# SDRAM.net
KiCad netlist of a schematic drawn in Altium Designer
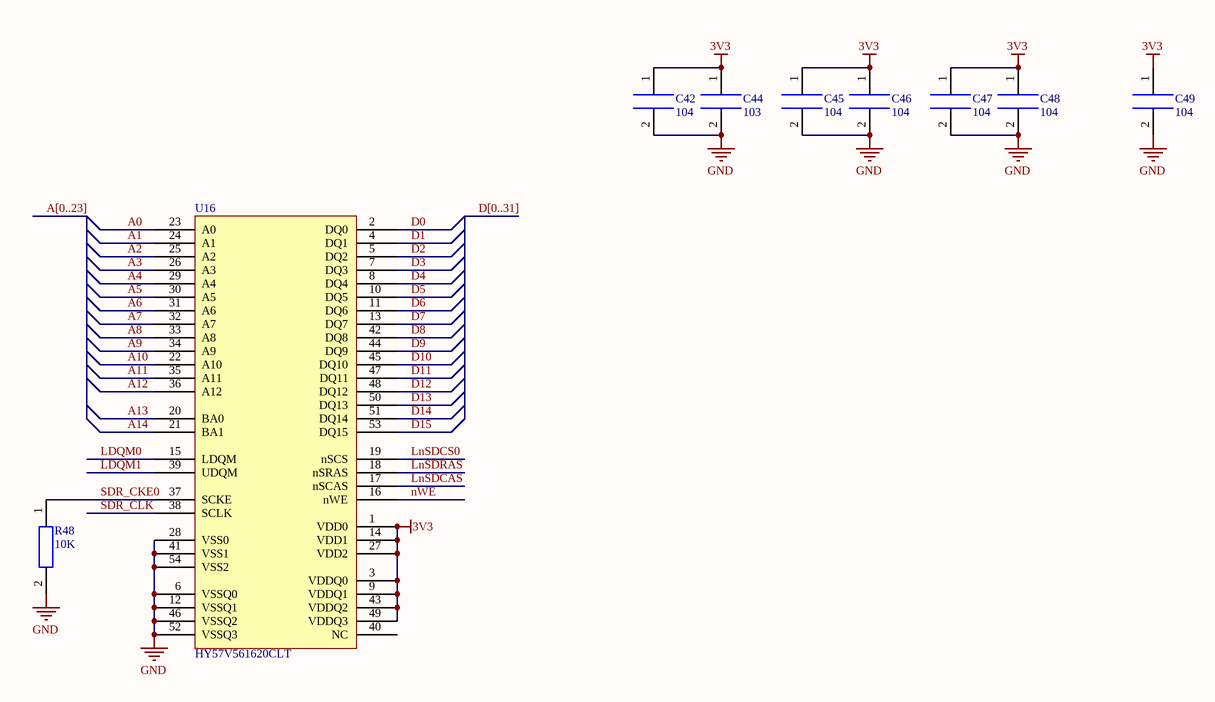
[diagram p0: SDRAM.SchDoc]

(export (version "E")
  (design (tool "Eeschema 10.0.6"))
  (components
    (comp (ref "C42") (value "104") (footprint "0603C") (libsource (lib "MyProject1") (part "CAP")))
    (comp (ref "C44") (value "103") (footprint "0603C") (libsource (lib "MyProject1") (part "CAP")))
    (comp (ref "C45") (value "104") (footprint "0603C") (libsource (lib "MyProject1") (part "CAP")))
    (comp (ref "C46") (value "104") (footprint "0603C") (libsource (lib "MyProject1") (part "CAP")))
    (comp (ref "C47") (value "104") (footprint "0603C") (libsource (lib "MyProject1") (part "CAP")))
    (comp (ref "C48") (value "104") (footprint "0603C") (libsource (lib "MyProject1") (part "CAP")))
    (comp (ref "C49") (value "104") (footprint "0603C") (libsource (lib "MyProject1") (part "CAP")))
    (comp (ref "R48") (value "10K") (footprint "0603R") (libsource (lib "MyProject1") (part "RES")))
    (comp (ref "U16")
      (value "HY57V561620CLT")
      (footprint "TSSOP-54")
      (libsource (lib "MyProject1") (part "HY57V561620CLT"))
    )
  )
  (nets
    (net (code "26") (name "/A0") (class "Default")
      (node (ref "U16") (pin "23") (pinfunction "A0_23") (pintype "passive"))
    )
    (net (code "27") (name "/A1") (class "Default")
      (node (ref "U16") (pin "24") (pinfunction "A1_24") (pintype "passive"))
    )
    (net (code "28") (name "/A2") (class "Default")
      (node (ref "U16") (pin "25") (pinfunction "A2_25") (pintype "passive"))
    )
    (net (code "29") (name "/A3") (class "Default")
      (node (ref "U16") (pin "26") (pinfunction "A3_26") (pintype "passive"))
    )
    (net (code "30") (name "/A4") (class "Default")
      (node (ref "U16") (pin "29") (pinfunction "A4_29") (pintype "passive"))
    )
    (net (code "31") (name "/A5") (class "Default")
      (node (ref "U16") (pin "30") (pinfunction "A5_30") (pintype "passive"))
    )
    (net (code "32") (name "/A6") (class "Default")
      (node (ref "U16") (pin "31") (pinfunction "A6_31") (pintype "passive"))
    )
    (net (code "33") (name "/A7") (class "Default")
      (node (ref "U16") (pin "32") (pinfunction "A7_32") (pintype "passive"))
    )
    (net (code "34") (name "/A8") (class "Default")
      (node (ref "U16") (pin "33") (pinfunction "A8_33") (pintype "passive"))
    )
    (net (code "35") (name "/A9") (class "Default")
      (node (ref "U16") (pin "34") (pinfunction "A9_34") (pintype "passive"))
    )
    (net (code "36") (name "/A10") (class "Default")
      (node (ref "U16") (pin "22") (pinfunction "A10_22") (pintype "passive"))
    )
    (net (code "37") (name "/A11") (class "Default")
      (node (ref "U16") (pin "35") (pinfunction "A11_35") (pintype "passive"))
    )
    (net (code "38") (name "/A12") (class "Default")
      (node (ref "U16") (pin "36") (pinfunction "A12_36") (pintype "passive"))
    )
    (net (code "39") (name "/A13") (class "Default")
      (node (ref "U16") (pin "20") (pinfunction "BA0_20") (pintype "passive"))
    )
    (net (code "40") (name "/A14") (class "Default")
      (node (ref "U16") (pin "21") (pinfunction "BA1_21") (pintype "passive"))
    )
    (net (code "42") (name "/D0") (class "Default")
      (node (ref "U16") (pin "2") (pinfunction "DQ0_2") (pintype "passive"))
    )
    (net (code "43") (name "/D1") (class "Default")
      (node (ref "U16") (pin "4") (pinfunction "DQ1_4") (pintype "passive"))
    )
    (net (code "44") (name "/D2") (class "Default")
      (node (ref "U16") (pin "5") (pinfunction "DQ2_5") (pintype "passive"))
    )
    (net (code "45") (name "/D3") (class "Default")
      (node (ref "U16") (pin "7") (pinfunction "DQ3_7") (pintype "passive"))
    )
    (net (code "46") (name "/D4") (class "Default")
      (node (ref "U16") (pin "8") (pinfunction "DQ4_8") (pintype "passive"))
    )
    (net (code "47") (name "/D5") (class "Default")
      (node (ref "U16") (pin "10") (pinfunction "DQ5_10") (pintype "passive"))
    )
    (net (code "48") (name "/D6") (class "Default")
      (node (ref "U16") (pin "11") (pinfunction "DQ6_11") (pintype "passive"))
    )
    (net (code "49") (name "/D7") (class "Default")
      (node (ref "U16") (pin "13") (pinfunction "DQ7_13") (pintype "passive"))
    )
    (net (code "50") (name "/D8") (class "Default")
      (node (ref "U16") (pin "42") (pinfunction "DQ8_42") (pintype "passive"))
    )
    (net (code "51") (name "/D9") (class "Default")
      (node (ref "U16") (pin "44") (pinfunction "DQ9_44") (pintype "passive"))
    )
    (net (code "52") (name "/D10") (class "Default")
      (node (ref "U16") (pin "45") (pinfunction "DQ10_45") (pintype "passive"))
    )
    (net (code "53") (name "/D11") (class "Default")
      (node (ref "U16") (pin "47") (pinfunction "DQ11_47") (pintype "passive"))
    )
    (net (code "54") (name "/D12") (class "Default")
      (node (ref "U16") (pin "48") (pinfunction "DQ12_48") (pintype "passive"))
    )
    (net (code "55") (name "/D13") (class "Default")
      (node (ref "U16") (pin "50") (pinfunction "DQ13_50") (pintype "passive"))
    )
    (net (code "56") (name "/D14") (class "Default")
      (node (ref "U16") (pin "51") (pinfunction "DQ14_51") (pintype "passive"))
    )
    (net (code "57") (name "/D15") (class "Default")
      (node (ref "U16") (pin "53") (pinfunction "DQ15_53") (pintype "passive"))
    )
    (net (code "59") (name "/LDQM0") (class "Default")
      (node (ref "U16") (pin "15") (pinfunction "LDQM_15") (pintype "passive"))
    )
    (net (code "60") (name "/LDQM1") (class "Default")
      (node (ref "U16") (pin "39") (pinfunction "UDQM_39") (pintype "passive"))
    )
    (net (code "61") (name "/LnSDCAS") (class "Default")
      (node (ref "U16") (pin "17") (pinfunction "nSCAS_17") (pintype "passive"))
    )
    (net (code "62") (name "/LnSDCS0") (class "Default")
      (node (ref "U16") (pin "19") (pinfunction "nSCS_19") (pintype "passive"))
    )
    (net (code "63") (name "/LnSDRAS") (class "Default")
      (node (ref "U16") (pin "18") (pinfunction "nSRAS_18") (pintype "passive"))
    )
    (net (code "64") (name "/SDR_CKE0") (class "Default")
      (node (ref "R48") (pin "1") (pinfunction "1_1") (pintype "passive"))
      (node (ref "U16") (pin "37") (pinfunction "SCKE_37") (pintype "passive"))
    )
    (net (code "65") (name "/SDR_CLK") (class "Default")
      (node (ref "U16") (pin "38") (pinfunction "SCLK_38") (pintype "passive"))
    )
    (net (code "66") (name "/nWE") (class "Default")
      (node (ref "U16") (pin "16") (pinfunction "nWE_16") (pintype "passive"))
    )
    (net (code "67") (name "3V3") (class "Default")
      (node (ref "C42") (pin "1") (pinfunction "1_1") (pintype "passive"))
      (node (ref "C44") (pin "1") (pinfunction "1_1") (pintype "passive"))
      (node (ref "C45") (pin "1") (pinfunction "1_1") (pintype "passive"))
      (node (ref "C46") (pin "1") (pinfunction "1_1") (pintype "passive"))
      (node (ref "C47") (pin "1") (pinfunction "1_1") (pintype "passive"))
      (node (ref "C48") (pin "1") (pinfunction "1_1") (pintype "passive"))
      (node (ref "C49") (pin "1") (pinfunction "1_1") (pintype "passive"))
      (node (ref "U16") (pin "1") (pinfunction "VDD0_1") (pintype "passive"))
      (node (ref "U16") (pin "14") (pinfunction "VDD1_14") (pintype "passive"))
      (node (ref "U16") (pin "27") (pinfunction "VDD2_27") (pintype "passive"))
      (node (ref "U16") (pin "3") (pinfunction "VDDQ0_3") (pintype "passive"))
      (node (ref "U16") (pin "43") (pinfunction "VDDQ2_43") (pintype "passive"))
      (node (ref "U16") (pin "49") (pinfunction "VDDQ3_49") (pintype "passive"))
      (node (ref "U16") (pin "9") (pinfunction "VDDQ1_9") (pintype "passive"))
    )
    (net (code "68") (name "GND") (class "Default")
      (node (ref "C42") (pin "2") (pinfunction "2_2") (pintype "passive"))
      (node (ref "C44") (pin "2") (pinfunction "2_2") (pintype "passive"))
      (node (ref "C45") (pin "2") (pinfunction "2_2") (pintype "passive"))
      (node (ref "C46") (pin "2") (pinfunction "2_2") (pintype "passive"))
      (node (ref "C47") (pin "2") (pinfunction "2_2") (pintype "passive"))
      (node (ref "C48") (pin "2") (pinfunction "2_2") (pintype "passive"))
      (node (ref "C49") (pin "2") (pinfunction "2_2") (pintype "passive"))
      (node (ref "R48") (pin "2") (pinfunction "2_2") (pintype "passive"))
      (node (ref "U16") (pin "12") (pinfunction "VSSQ1_12") (pintype "passive"))
      (node (ref "U16") (pin "28") (pinfunction "VSS0_28") (pintype "passive"))
      (node (ref "U16") (pin "41") (pinfunction "VSS1_41") (pintype "passive"))
      (node (ref "U16") (pin "46") (pinfunction "VSSQ2_46") (pintype "passive"))
      (node (ref "U16") (pin "52") (pinfunction "VSSQ3_52") (pintype "passive"))
      (node (ref "U16") (pin "54") (pinfunction "VSS2_54") (pintype "passive"))
      (node (ref "U16") (pin "6") (pinfunction "VSSQ0_6") (pintype "passive"))
    )
    (net (code "69") (name "unconnected-(U16-NC-Pad40)") (class "Default")
      (node (ref "U16") (pin "40") (pinfunction "NC_40") (pintype "passive"))
    )
  )
)
